# SCH_battery_monitoring_system_updated_20.net
KiCad netlist of a schematic drawn in EasyEDA
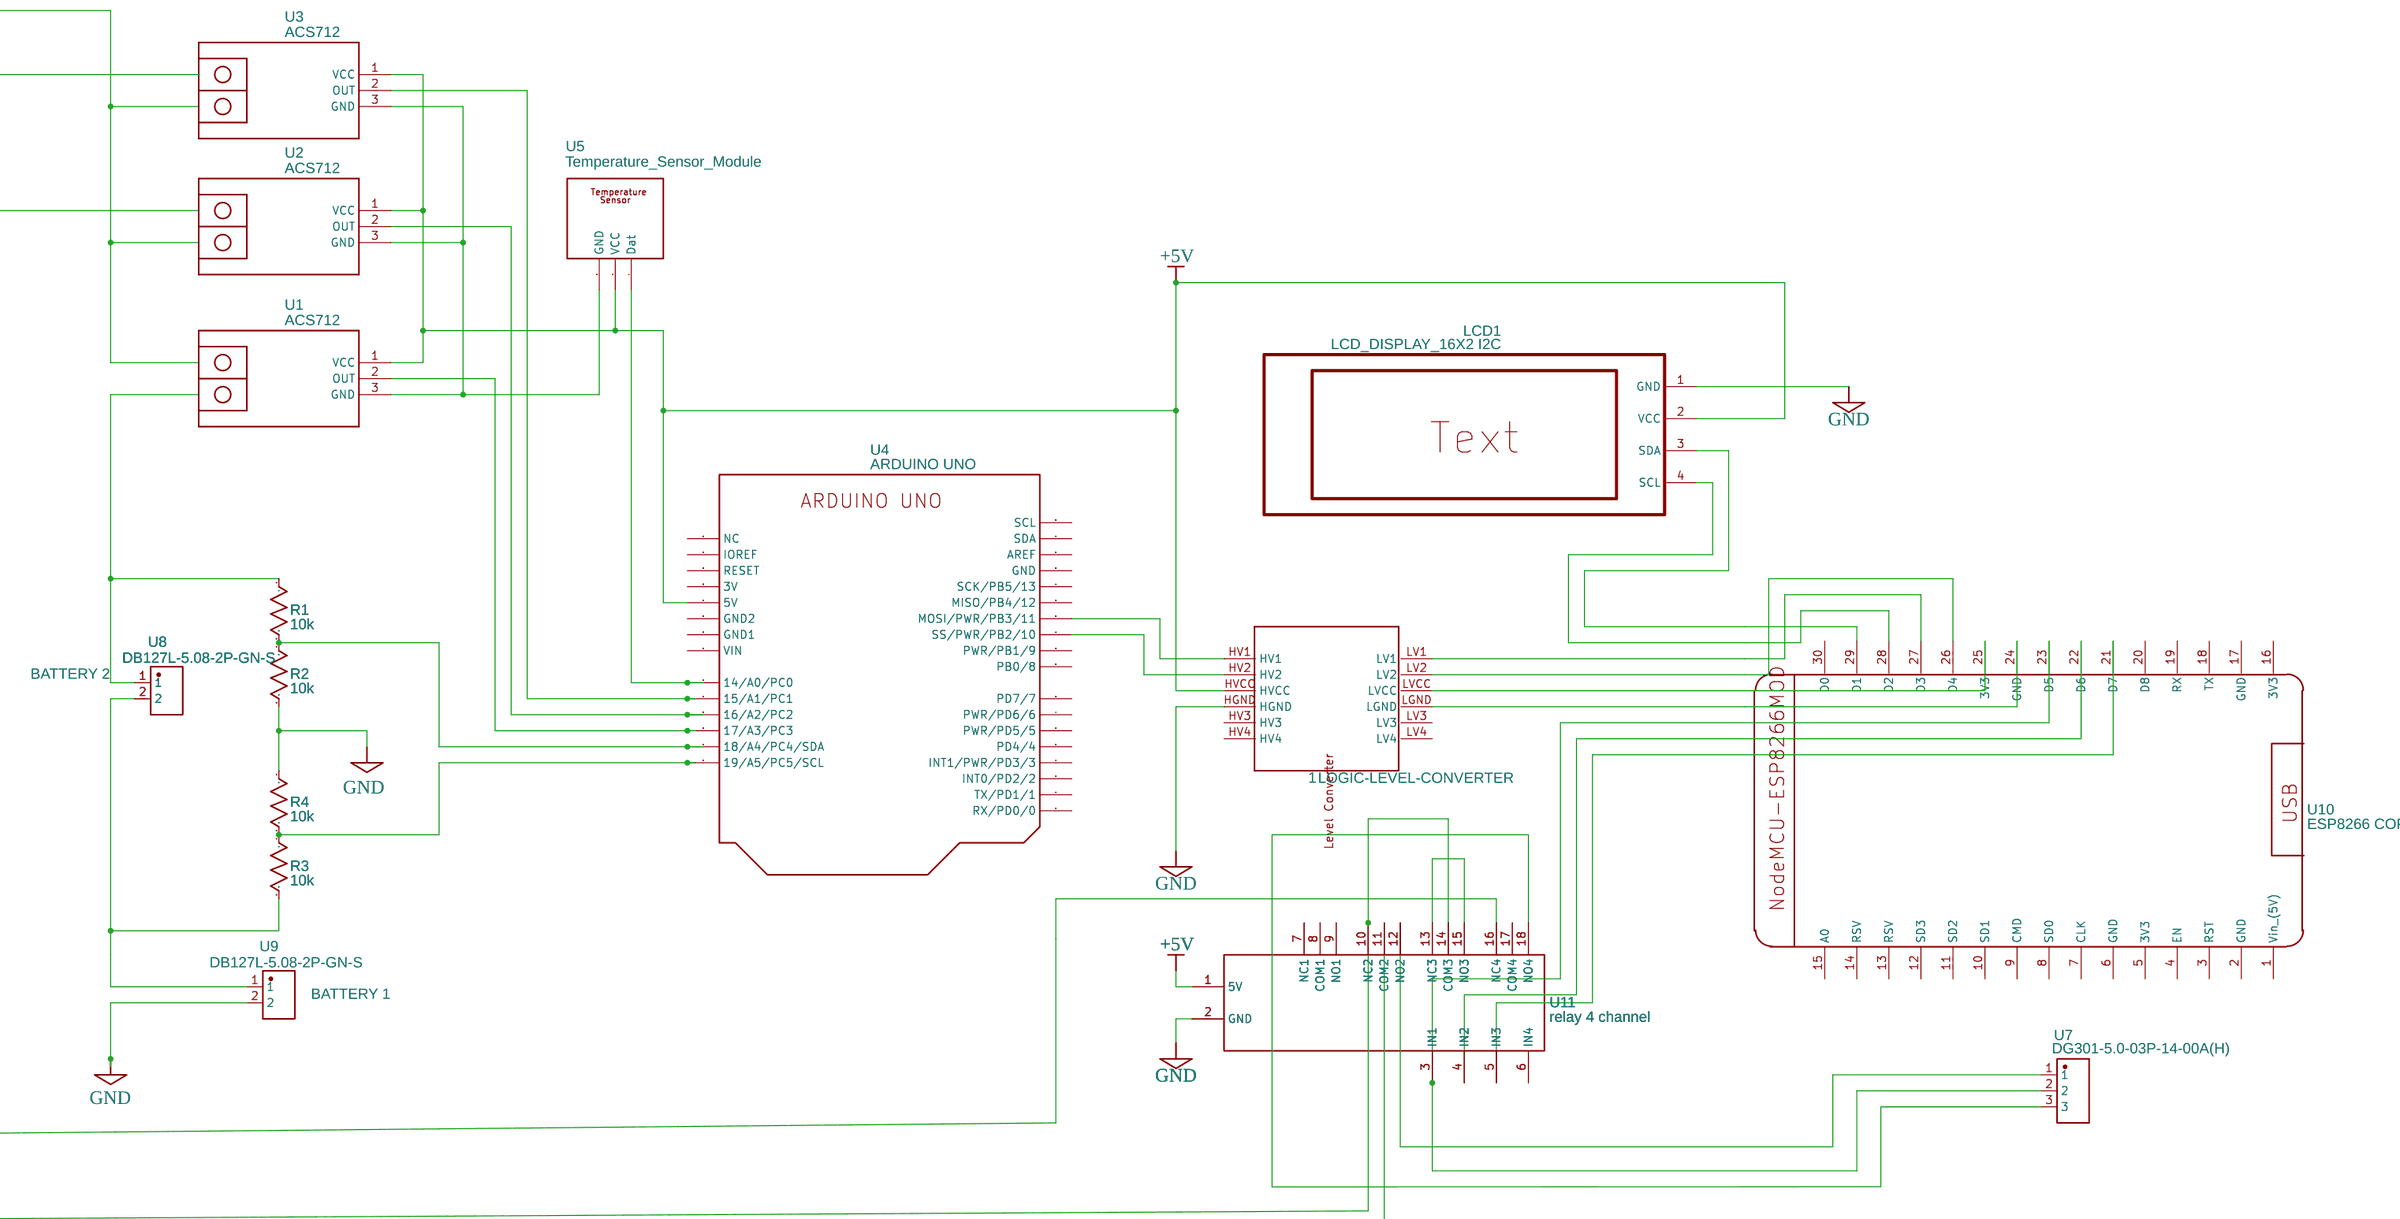
[diagram p0: schematic sheet]

(export (version "E")
  (design (tool "Eeschema 10.0.6"))
  (components
    (comp (ref "1") (value "LOGIC-LEVEL-CONVERTER") (libsource (lib "") (part "LOGIC-LEVEL-CONVERTER")))
    (comp (ref "LCD1") (value "LCD_DISPLAY_16X2 I2C") (libsource (lib "") (part "LCD_DISPLAY_16X2 I2C")))
    (comp (ref "R1") (value "10k") (libsource (lib "") (part "R_0603_US")))
    (comp (ref "R2") (value "10k") (libsource (lib "") (part "R_0603_US")))
    (comp (ref "R3") (value "10k") (libsource (lib "") (part "R_0603_US")))
    (comp (ref "R4") (value "10k") (libsource (lib "") (part "R_0603_US")))
    (comp (ref "U1") (value "ACS712") (libsource (lib "") (part "CURRENT-SENSOR-ACS712")))
    (comp (ref "U2") (value "ACS712") (libsource (lib "") (part "CURRENT-SENSOR-ACS712")))
    (comp (ref "U3") (value "ACS712") (libsource (lib "") (part "CURRENT-SENSOR-ACS712")))
    (comp (ref "U4") (value "ARDUINO UNO") (libsource (lib "") (part "ARDUINO UNO")))
    (comp (ref "U5")
      (value "Temperature_Sensor_Module")
      (libsource (lib "") (part "DS18B20_Temperature_Sensor_Module"))
    )
    (comp (ref "U7")
      (value "DG301-5.0-03P-14-00A(H)")
      (fields (field (name "Manufacturer") "DEGSON（高正/高松）"))
      (libsource (lib "") (part "DG301-5.0-03P-14-00A(H)"))
    )
    (comp (ref "U8")
      (value "DB127L-5.08-2P-GN-S")
      (fields (field (name "Manufacturer") "DORABO(地博电气)"))
      (libsource (lib "") (part "DB127L-5.08-2P-GN-S"))
    )
    (comp (ref "U9")
      (value "DB127L-5.08-2P-GN-S")
      (fields (field (name "Manufacturer") "DORABO(地博电气)"))
      (libsource (lib "") (part "DB127L-5.08-2P-GN-S"))
    )
    (comp (ref "U10")
      (value "ESP8266 COPY")
      (fields
        (field (name "BOM_Manufacturer Part") "NodeMCU-8266Lua")
        (field (name "BOM_Supplier Part") "C111436")
      )
      (libsource (lib "") (part "ESP8266 COPY"))
    )
    (comp (ref "U11") (value "relay 4 channel") (libsource (lib "") (part "relay 4 channel")))
  )
  (nets
    (net (code "1") (name "+5V") (class "Default")
      (node (ref "1") (pin "HVCC") (pinfunction "HVCC_HVCC") (pintype "bidirectional"))
      (node (ref "LCD1") (pin "2") (pinfunction "VCC_2") (pintype "passive"))
      (node (ref "U1") (pin "1") (pinfunction "VCC_1") (pintype "passive"))
      (node (ref "U11") (pin "1") (pinfunction "5V_1") (pintype "unspecified"))
      (node (ref "U2") (pin "1") (pinfunction "VCC_1") (pintype "passive"))
      (node (ref "U3") (pin "1") (pinfunction "VCC_1") (pintype "passive"))
      (node (ref "U4") (pin "28") (pinfunction "5V_28") (pintype "passive"))
      (node (ref "U5") (pin "2") (pinfunction "VCC_2") (pintype "unspecified"))
    )
    (net (code "2") (name "GND") (class "Default")
      (node (ref "1") (pin "HGND") (pinfunction "HGND_HGND") (pintype "bidirectional"))
      (node (ref "LCD1") (pin "1") (pinfunction "GND_1") (pintype "passive"))
      (node (ref "R2") (pin "2") (pinfunction "2_2") (pintype "unspecified"))
      (node (ref "R4") (pin "1") (pinfunction "1_1") (pintype "unspecified"))
      (node (ref "U11") (pin "2") (pinfunction "GND_2") (pintype "unspecified"))
      (node (ref "U9") (pin "2") (pinfunction "2_2") (pintype "unspecified"))
    )
    (net (code "3") (name "Net-(1-PadLGND)") (class "Default")
      (node (ref "1") (pin "LGND") (pinfunction "LGND_LGND") (pintype "bidirectional"))
      (node (ref "U10") (pin "24") (pinfunction "GND_24") (pintype "unspecified"))
    )
    (net (code "4") (name "Net-(1-PadLVCC)") (class "Default")
      (node (ref "1") (pin "LVCC") (pinfunction "LVCC_LVCC") (pintype "bidirectional"))
      (node (ref "U10") (pin "25") (pinfunction "3V3_25") (pintype "unspecified"))
    )
    (net (code "5") (name "Net-(LCD1-SCL)") (class "Default")
      (node (ref "LCD1") (pin "4") (pinfunction "SCL_4") (pintype "passive"))
      (node (ref "U10") (pin "28") (pinfunction "D2_28") (pintype "unspecified"))
    )
    (net (code "6") (name "Net-(LCD1-SDA)") (class "Default")
      (node (ref "LCD1") (pin "3") (pinfunction "SDA_3") (pintype "passive"))
      (node (ref "U10") (pin "29") (pinfunction "D1_29") (pintype "unspecified"))
    )
    (net (code "7") (name "Net-(R1-Pad1)") (class "Default")
      (node (ref "R1") (pin "1") (pinfunction "1_1") (pintype "unspecified"))
      (node (ref "U8") (pin "1") (pinfunction "1_1") (pintype "unspecified"))
    )
    (net (code "8") (name "Net-(R3-Pad2)") (class "Default")
      (node (ref "R3") (pin "2") (pinfunction "2_2") (pintype "unspecified"))
      (node (ref "U8") (pin "2") (pinfunction "2_2") (pintype "unspecified"))
      (node (ref "U9") (pin "1") (pinfunction "1_1") (pintype "unspecified"))
    )
    (net (code "9") (name "Net-(U1-GND)") (class "Default")
      (node (ref "U1") (pin "3") (pinfunction "GND_3") (pintype "passive"))
      (node (ref "U2") (pin "3") (pinfunction "GND_3") (pintype "passive"))
      (node (ref "U3") (pin "3") (pinfunction "GND_3") (pintype "passive"))
      (node (ref "U5") (pin "3") (pinfunction "GND_3") (pintype "unspecified"))
    )
    (net (code "10") (name "Net-(U1-OUT)") (class "Default")
      (node (ref "U1") (pin "2") (pinfunction "OUT_2") (pintype "output"))
      (node (ref "U4") (pin "21") (pinfunction "17/A3/PC3_21") (pintype "unspecified"))
    )
    (net (code "11") (name "Net-(U2-OUT)") (class "Default")
      (node (ref "U2") (pin "2") (pinfunction "OUT_2") (pintype "output"))
      (node (ref "U4") (pin "22") (pinfunction "16/A2/PC2_22") (pintype "unspecified"))
    )
    (net (code "12") (name "Net-(U3-OUT)") (class "Default")
      (node (ref "U3") (pin "2") (pinfunction "OUT_2") (pintype "output"))
      (node (ref "U4") (pin "23") (pinfunction "15/A1/PC1_23") (pintype "unspecified"))
    )
    (net (code "13") (name "Net-(U4-14{slash}A0{slash}PC0)") (class "Default")
      (node (ref "U4") (pin "24") (pinfunction "14/A0/PC0_24") (pintype "unspecified"))
      (node (ref "U5") (pin "1") (pinfunction "Dat_1") (pintype "unspecified"))
    )
    (net (code "14") (name "Net-(U4-18{slash}A4{slash}PC4{slash}SDA)") (class "Default")
      (node (ref "R1") (pin "2") (pinfunction "2_2") (pintype "unspecified"))
      (node (ref "R2") (pin "1") (pinfunction "1_1") (pintype "unspecified"))
      (node (ref "U4") (pin "20") (pinfunction "18/A4/PC4/SDA_20") (pintype "unspecified"))
    )
    (net (code "15") (name "Net-(U4-19{slash}A5{slash}PC5{slash}SCL)") (class "Default")
      (node (ref "R3") (pin "1") (pinfunction "1_1") (pintype "unspecified"))
      (node (ref "R4") (pin "2") (pinfunction "2_2") (pintype "unspecified"))
      (node (ref "U4") (pin "19") (pinfunction "19/A5/PC5/SCL_19") (pintype "unspecified"))
    )
    (net (code "16") (name "Net-(U4-MOSI{slash}PWR{slash}PB3{slash}11)") (class "Default")
      (node (ref "1") (pin "HV1") (pinfunction "HV1_HV1") (pintype "bidirectional"))
      (node (ref "U4") (pin "12") (pinfunction "MOSI/PWR/PB3/11_12") (pintype "unspecified"))
    )
    (net (code "17") (name "Net-(U4-SS{slash}PWR{slash}PB2{slash}10)") (class "Default")
      (node (ref "1") (pin "HV2") (pinfunction "HV2_HV2") (pintype "bidirectional"))
      (node (ref "U4") (pin "11") (pinfunction "SS/PWR/PB2/10_11") (pintype "unspecified"))
    )
    (net (code "18") (name "Net-(U10-D3)") (class "Default")
      (node (ref "1") (pin "LV1") (pinfunction "LV1_LV1") (pintype "bidirectional"))
      (node (ref "U10") (pin "27") (pinfunction "D3_27") (pintype "unspecified"))
    )
    (net (code "19") (name "Net-(U10-D4)") (class "Default")
      (node (ref "1") (pin "LV2") (pinfunction "LV2_LV2") (pintype "bidirectional"))
      (node (ref "U10") (pin "26") (pinfunction "D4_26") (pintype "unspecified"))
    )
    (net (code "20") (name "Net-(U10-D5)") (class "Default")
      (node (ref "U10") (pin "23") (pinfunction "D5_23") (pintype "unspecified"))
      (node (ref "U11") (pin "3") (pinfunction "IN1_3") (pintype "unspecified"))
      (node (ref "U7") (pin "2") (pinfunction "2_2") (pintype "unspecified"))
    )
    (net (code "21") (name "Net-(U10-D6)") (class "Default")
      (node (ref "U10") (pin "22") (pinfunction "D6_22") (pintype "unspecified"))
      (node (ref "U11") (pin "4") (pinfunction "IN2_4") (pintype "unspecified"))
    )
    (net (code "22") (name "Net-(U10-D7)") (class "Default")
      (node (ref "U10") (pin "21") (pinfunction "D7_21") (pintype "unspecified"))
      (node (ref "U11") (pin "5") (pinfunction "IN3_5") (pintype "unspecified"))
    )
    (net (code "23") (name "Net-(U11-COM3)") (class "Default")
      (node (ref "U11") (pin "10") (pinfunction "NC2_10") (pintype "unspecified"))
      (node (ref "U11") (pin "14") (pinfunction "COM3_14") (pintype "unspecified"))
    )
    (net (code "24") (name "Net-(U11-NC3)") (class "Default")
      (node (ref "U11") (pin "13") (pinfunction "NC3_13") (pintype "unspecified"))
      (node (ref "U11") (pin "15") (pinfunction "NO3_15") (pintype "unspecified"))
    )
    (net (code "25") (name "Net-(U11-NO2)") (class "Default")
      (node (ref "U11") (pin "12") (pinfunction "NO2_12") (pintype "unspecified"))
      (node (ref "U7") (pin "1") (pinfunction "1_1") (pintype "unspecified"))
    )
    (net (code "26") (name "Net-(U11-NO4)") (class "Default")
      (node (ref "U11") (pin "18") (pinfunction "NO4_18") (pintype "unspecified"))
      (node (ref "U7") (pin "3") (pinfunction "3_3") (pintype "unspecified"))
    )
    (net (code "27") (name "unconnected-(1-PadHV3)") (class "Default")
      (node (ref "1") (pin "HV3") (pinfunction "HV3_HV3") (pintype "bidirectional"))
    )
    (net (code "28") (name "unconnected-(1-PadHV4)") (class "Default")
      (node (ref "1") (pin "HV4") (pinfunction "HV4_HV4") (pintype "bidirectional"))
    )
    (net (code "29") (name "unconnected-(1-PadLV3)") (class "Default")
      (node (ref "1") (pin "LV3") (pinfunction "LV3_LV3") (pintype "bidirectional"))
    )
    (net (code "30") (name "unconnected-(1-PadLV4)") (class "Default")
      (node (ref "1") (pin "LV4") (pinfunction "LV4_LV4") (pintype "bidirectional"))
    )
    (net (code "31") (name "unconnected-(U4-3V-Pad29)") (class "Default")
      (node (ref "U4") (pin "29") (pinfunction "3V_29") (pintype "passive"))
    )
    (net (code "32") (name "unconnected-(U4-AREF-Pad16)") (class "Default")
      (node (ref "U4") (pin "16") (pinfunction "AREF_16") (pintype "unspecified"))
    )
    (net (code "33") (name "unconnected-(U4-GND-Pad15)") (class "Default")
      (node (ref "U4") (pin "15") (pinfunction "GND_15") (pintype "passive"))
    )
    (net (code "34") (name "unconnected-(U4-GND1-Pad26)") (class "Default")
      (node (ref "U4") (pin "26") (pinfunction "GND1_26") (pintype "passive"))
    )
    (net (code "35") (name "unconnected-(U4-GND2-Pad27)") (class "Default")
      (node (ref "U4") (pin "27") (pinfunction "GND2_27") (pintype "passive"))
    )
    (net (code "36") (name "unconnected-(U4-INT0{slash}PD2{slash}2-Pad3)") (class "Default")
      (node (ref "U4") (pin "3") (pinfunction "INT0/PD2/2_3") (pintype "unspecified"))
    )
    (net (code "37") (name "unconnected-(U4-INT1{slash}PWR{slash}PD3{slash}3-Pad4)") (class "Default")
      (node (ref "U4") (pin "4") (pinfunction "INT1/PWR/PD3/3_4") (pintype "unspecified"))
    )
    (net (code "38") (name "unconnected-(U4-IOREF-Pad31)") (class "Default")
      (node (ref "U4") (pin "31") (pinfunction "IOREF_31") (pintype "unspecified"))
    )
    (net (code "39") (name "unconnected-(U4-MISO{slash}PB4{slash}12-Pad13)") (class "Default")
      (node (ref "U4") (pin "13") (pinfunction "MISO/PB4/12_13") (pintype "unspecified"))
    )
    (net (code "40") (name "unconnected-(U4-NC-Pad32)") (class "Default")
      (node (ref "U4") (pin "32") (pinfunction "NC_32") (pintype "unspecified"))
    )
    (net (code "41") (name "unconnected-(U4-PB0{slash}8-Pad9)") (class "Default")
      (node (ref "U4") (pin "9") (pinfunction "PB0/8_9") (pintype "unspecified"))
    )
    (net (code "42") (name "unconnected-(U4-PD4{slash}4-Pad5)") (class "Default")
      (node (ref "U4") (pin "5") (pinfunction "PD4/4_5") (pintype "unspecified"))
    )
    (net (code "43") (name "unconnected-(U4-PD7{slash}7-Pad8)") (class "Default")
      (node (ref "U4") (pin "8") (pinfunction "PD7/7_8") (pintype "unspecified"))
    )
    (net (code "44") (name "unconnected-(U4-PWR{slash}PB1{slash}9-Pad10)") (class "Default")
      (node (ref "U4") (pin "10") (pinfunction "PWR/PB1/9_10") (pintype "unspecified"))
    )
    (net (code "45") (name "unconnected-(U4-PWR{slash}PD5{slash}5-Pad6)") (class "Default")
      (node (ref "U4") (pin "6") (pinfunction "PWR/PD5/5_6") (pintype "unspecified"))
    )
    (net (code "46") (name "unconnected-(U4-PWR{slash}PD6{slash}6-Pad7)") (class "Default")
      (node (ref "U4") (pin "7") (pinfunction "PWR/PD6/6_7") (pintype "unspecified"))
    )
    (net (code "47") (name "unconnected-(U4-RESET-Pad30)") (class "Default")
      (node (ref "U4") (pin "30") (pinfunction "RESET_30") (pintype "unspecified"))
    )
    (net (code "48") (name "unconnected-(U4-RX{slash}PD0{slash}0-Pad1)") (class "Default")
      (node (ref "U4") (pin "1") (pinfunction "RX/PD0/0_1") (pintype "unspecified"))
    )
    (net (code "49") (name "unconnected-(U4-SCK{slash}PB5{slash}13-Pad14)") (class "Default")
      (node (ref "U4") (pin "14") (pinfunction "SCK/PB5/13_14") (pintype "unspecified"))
    )
    (net (code "50") (name "unconnected-(U4-SCL-Pad18)") (class "Default")
      (node (ref "U4") (pin "18") (pinfunction "SCL_18") (pintype "unspecified"))
    )
    (net (code "51") (name "unconnected-(U4-SDA-Pad17)") (class "Default")
      (node (ref "U4") (pin "17") (pinfunction "SDA_17") (pintype "unspecified"))
    )
    (net (code "52") (name "unconnected-(U4-TX{slash}PD1{slash}1-Pad2)") (class "Default")
      (node (ref "U4") (pin "2") (pinfunction "TX/PD1/1_2") (pintype "unspecified"))
    )
    (net (code "53") (name "unconnected-(U4-VIN-Pad25)") (class "Default")
      (node (ref "U4") (pin "25") (pinfunction "VIN_25") (pintype "passive"))
    )
    (net (code "54") (name "unconnected-(U10-3V3-Pad5)") (class "Default")
      (node (ref "U10") (pin "5") (pinfunction "3V3_5") (pintype "unspecified"))
    )
    (net (code "55") (name "unconnected-(U10-3V3-Pad16)") (class "Default")
      (node (ref "U10") (pin "16") (pinfunction "3V3_16") (pintype "unspecified"))
    )
    (net (code "56") (name "unconnected-(U10-A0-Pad15)") (class "Default")
      (node (ref "U10") (pin "15") (pinfunction "A0_15") (pintype "unspecified"))
    )
    (net (code "57") (name "unconnected-(U10-CLK-Pad7)") (class "Default")
      (node (ref "U10") (pin "7") (pinfunction "CLK_7") (pintype "unspecified"))
    )
    (net (code "58") (name "unconnected-(U10-CMD-Pad9)") (class "Default")
      (node (ref "U10") (pin "9") (pinfunction "CMD_9") (pintype "unspecified"))
    )
    (net (code "59") (name "unconnected-(U10-D0-Pad30)") (class "Default")
      (node (ref "U10") (pin "30") (pinfunction "D0_30") (pintype "unspecified"))
    )
    (net (code "60") (name "unconnected-(U10-D8-Pad20)") (class "Default")
      (node (ref "U10") (pin "20") (pinfunction "D8_20") (pintype "unspecified"))
    )
    (net (code "61") (name "unconnected-(U10-EN-Pad4)") (class "Default")
      (node (ref "U10") (pin "4") (pinfunction "EN_4") (pintype "unspecified"))
    )
    (net (code "62") (name "unconnected-(U10-GND-Pad2)") (class "Default")
      (node (ref "U10") (pin "2") (pinfunction "GND_2") (pintype "unspecified"))
    )
    (net (code "63") (name "unconnected-(U10-GND-Pad6)") (class "Default")
      (node (ref "U10") (pin "6") (pinfunction "GND_6") (pintype "unspecified"))
    )
    (net (code "64") (name "unconnected-(U10-GND-Pad17)") (class "Default")
      (node (ref "U10") (pin "17") (pinfunction "GND_17") (pintype "unspecified"))
    )
    (net (code "65") (name "unconnected-(U10-RST-Pad3)") (class "Default")
      (node (ref "U10") (pin "3") (pinfunction "RST_3") (pintype "unspecified"))
    )
    (net (code "66") (name "unconnected-(U10-RSV-Pad13)") (class "Default")
      (node (ref "U10") (pin "13") (pinfunction "RSV_13") (pintype "unspecified"))
    )
    (net (code "67") (name "unconnected-(U10-RSV-Pad14)") (class "Default")
      (node (ref "U10") (pin "14") (pinfunction "RSV_14") (pintype "unspecified"))
    )
    (net (code "68") (name "unconnected-(U10-RX-Pad19)") (class "Default")
      (node (ref "U10") (pin "19") (pinfunction "RX_19") (pintype "unspecified"))
    )
    (net (code "69") (name "unconnected-(U10-SD0-Pad8)") (class "Default")
      (node (ref "U10") (pin "8") (pinfunction "SD0_8") (pintype "unspecified"))
    )
    (net (code "70") (name "unconnected-(U10-SD1-Pad10)") (class "Default")
      (node (ref "U10") (pin "10") (pinfunction "SD1_10") (pintype "unspecified"))
    )
    (net (code "71") (name "unconnected-(U10-SD2-Pad11)") (class "Default")
      (node (ref "U10") (pin "11") (pinfunction "SD2_11") (pintype "unspecified"))
    )
    (net (code "72") (name "unconnected-(U10-SD3-Pad12)") (class "Default")
      (node (ref "U10") (pin "12") (pinfunction "SD3_12") (pintype "unspecified"))
    )
    (net (code "73") (name "unconnected-(U10-TX-Pad18)") (class "Default")
      (node (ref "U10") (pin "18") (pinfunction "TX_18") (pintype "unspecified"))
    )
    (net (code "74") (name "unconnected-(U10-Vin_(5V)-Pad1)") (class "Default")
      (node (ref "U10") (pin "1") (pinfunction "Vin_(5V)_1") (pintype "unspecified"))
    )
    (net (code "75") (name "unconnected-(U11-COM1-Pad8)") (class "Default")
      (node (ref "U11") (pin "8") (pinfunction "COM1_8") (pintype "unspecified"))
    )
    (net (code "76") (name "unconnected-(U11-COM2-Pad11)") (class "Default")
      (node (ref "U11") (pin "11") (pinfunction "COM2_11") (pintype "unspecified"))
    )
    (net (code "77") (name "unconnected-(U11-COM4-Pad17)") (class "Default")
      (node (ref "U11") (pin "17") (pinfunction "COM4_17") (pintype "unspecified"))
    )
    (net (code "78") (name "unconnected-(U11-IN4-Pad6)") (class "Default")
      (node (ref "U11") (pin "6") (pinfunction "IN4_6") (pintype "unspecified"))
    )
    (net (code "79") (name "unconnected-(U11-NC1-Pad7)") (class "Default")
      (node (ref "U11") (pin "7") (pinfunction "NC1_7") (pintype "unspecified"))
    )
    (net (code "80") (name "unconnected-(U11-NC4-Pad16)") (class "Default")
      (node (ref "U11") (pin "16") (pinfunction "NC4_16") (pintype "unspecified"))
    )
    (net (code "81") (name "unconnected-(U11-NO1-Pad9)") (class "Default")
      (node (ref "U11") (pin "9") (pinfunction "NO1_9") (pintype "unspecified"))
    )
  )
)
